# usb.net
KiCad netlist of a schematic drawn in Altium Designer
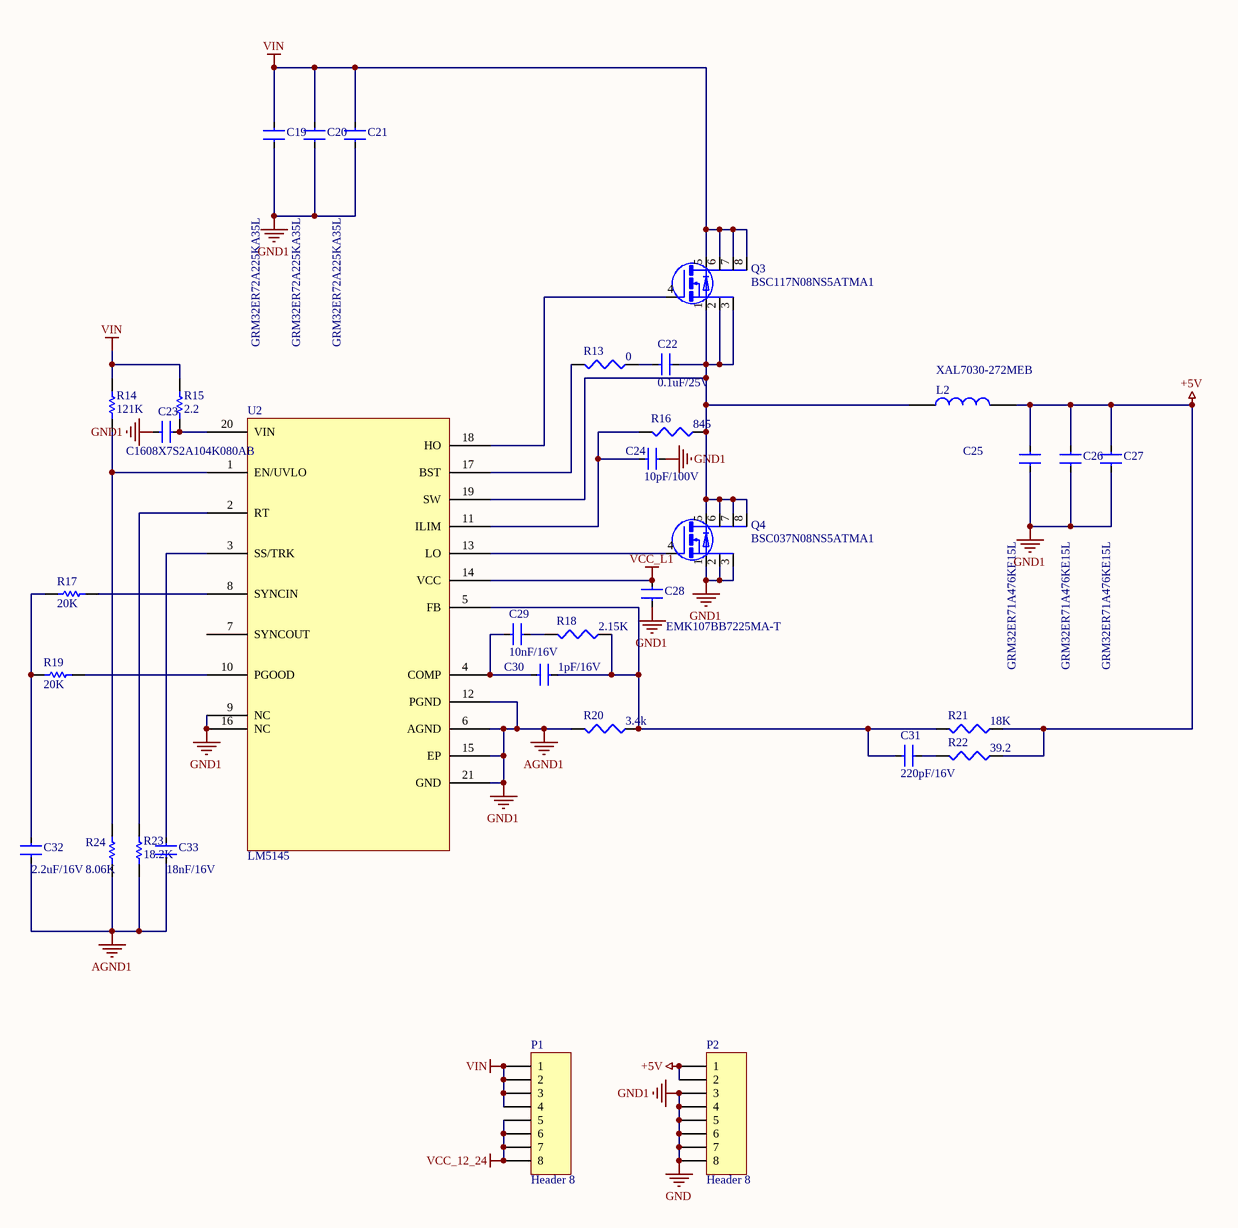
[diagram p0: usb.SchDoc]

(export (version "E")
  (design (tool "Eeschema 10.0.6"))
  (components
    (comp (ref "C19")
      (value "GRM32ER72A225KA35L")
      (footprint "1210C")
      (description "CCX85-103")
      (libsource (lib "无极性电容") (part "0.01UF"))
    )
    (comp (ref "C20")
      (value "GRM32ER72A225KA35L")
      (footprint "1210C")
      (description "CCX85-103")
      (libsource (lib "无极性电容") (part "0.01UF"))
    )
    (comp (ref "C21")
      (value "GRM32ER72A225KA35L")
      (footprint "1210C")
      (description "CCX85-103")
      (libsource (lib "无极性电容") (part "0.01UF"))
    )
    (comp (ref "C22")
      (value "0.1uF/25V")
      (footprint "0603C")
      (description "CCX85-103")
      (libsource (lib "无极性电容") (part "0.01UF"))
    )
    (comp (ref "C23")
      (value "C1608X7S2A104K080AB")
      (footprint "0603C")
      (description "CCX85-103")
      (libsource (lib "无极性电容") (part "0.01UF"))
    )
    (comp (ref "C24")
      (value "10pF/100V")
      (footprint "0603C")
      (description "CCX85-103")
      (libsource (lib "无极性电容") (part "0.01UF"))
    )
    (comp (ref "C25")
      (value "GRM32ER71A476KE15L")
      (footprint "1210C")
      (description "CCX85-103")
      (libsource (lib "无极性电容") (part "0.01UF"))
    )
    (comp (ref "C26")
      (value "GRM32ER71A476KE15L")
      (footprint "1210C")
      (description "CCX85-103")
      (libsource (lib "无极性电容") (part "0.01UF"))
    )
    (comp (ref "C27")
      (value "GRM32ER71A476KE15L")
      (footprint "1210C")
      (description "CCX85-103")
      (libsource (lib "无极性电容") (part "0.01UF"))
    )
    (comp (ref "C28")
      (value "EMK107BB7225MA-T")
      (footprint "0603C")
      (description "CCX85-103")
      (libsource (lib "无极性电容") (part "0.01UF"))
    )
    (comp (ref "C29")
      (value "10nF/16V")
      (footprint "0603C")
      (description "CCX85-103")
      (libsource (lib "无极性电容") (part "0.01UF"))
    )
    (comp (ref "C30")
      (value "1pF/16V")
      (footprint "0603C")
      (description "CCX85-103")
      (libsource (lib "无极性电容") (part "0.01UF"))
    )
    (comp (ref "C31")
      (value "220pF/16V")
      (footprint "0603C")
      (description "CCX85-103")
      (libsource (lib "无极性电容") (part "0.01UF"))
    )
    (comp (ref "C32")
      (value "2.2uF/16V")
      (footprint "0603C")
      (description "CCX85-103")
      (libsource (lib "无极性电容") (part "0.01UF"))
    )
    (comp (ref "C33")
      (value "18nF/16V")
      (footprint "0603C")
      (description "CCX85-103")
      (libsource (lib "无极性电容") (part "0.01UF"))
    )
    (comp (ref "L2") (value "XAL7030-272MEB") (footprint "XAL7030") (libsource (lib "*") (part "INDUCTOR")))
    (comp (ref "P1")
      (value "Header 8")
      (footprint "CH3.96-8P")
      (description "Header, 8-Pin")
      (fields (field (name "PUBLISHER") "Altium Limited"))
      (libsource (lib "Miscellaneous Connectors") (part "Header 8"))
    )
    (comp (ref "P2")
      (value "Header 8")
      (footprint "CH3.96-8P")
      (description "Header, 8-Pin")
      (fields (field (name "PUBLISHER") "Altium Limited"))
      (libsource (lib "Miscellaneous Connectors") (part "Header 8"))
    )
    (comp (ref "Q3")
      (value "BSC117N08NS5ATMA1")
      (footprint "PowerPAK SO-8")
      (description "Si4004DY")
      (libsource (lib "Schlib_20110825") (part "Si4004DY"))
    )
    (comp (ref "Q4")
      (value "BSC037N08NS5ATMA1")
      (footprint "PowerPAK SO-8")
      (description "Si4004DY")
      (libsource (lib "Schlib_20110825") (part "Si4004DY"))
    )
    (comp (ref "R13")
      (value "0")
      (footprint "0603R")
      (description "Resistor")
      (fields (field (name "PUBLISHER") "Altium Limited"))
      (libsource (lib "SM") (part "Res3"))
    )
    (comp (ref "R14")
      (value "121K")
      (footprint "0805R")
      (description "Semiconductor Resistor")
      (fields (field (name "PUBLISHER") "Altium Limited"))
      (libsource (lib "Miscellaneous Devices") (part "Res Semi"))
    )
    (comp (ref "R15")
      (value "2.2")
      (footprint "0603R")
      (description "Semiconductor Resistor")
      (fields (field (name "PUBLISHER") "Altium Limited"))
      (libsource (lib "Miscellaneous Devices") (part "Res Semi"))
    )
    (comp (ref "R16")
      (value "845")
      (footprint "0603R")
      (description "Resistor")
      (fields (field (name "PUBLISHER") "Altium Limited"))
      (libsource (lib "SM") (part "Res3"))
    )
    (comp (ref "R17")
      (value "20K")
      (footprint "0603R")
      (description "Semiconductor Resistor")
      (fields (field (name "PUBLISHER") "Altium Limited"))
      (libsource (lib "Miscellaneous Devices") (part "Res Semi"))
    )
    (comp (ref "R18")
      (value "2.15K")
      (footprint "0603R")
      (description "Resistor")
      (fields (field (name "PUBLISHER") "Altium Limited"))
      (libsource (lib "SM") (part "Res3"))
    )
    (comp (ref "R19")
      (value "20K")
      (footprint "0603R")
      (description "Semiconductor Resistor")
      (fields (field (name "PUBLISHER") "Altium Limited"))
      (libsource (lib "Miscellaneous Devices") (part "Res Semi"))
    )
    (comp (ref "R20")
      (value "3.4k")
      (footprint "0603R")
      (description "Resistor")
      (fields (field (name "PUBLISHER") "Altium Limited"))
      (libsource (lib "SM") (part "Res3"))
    )
    (comp (ref "R21")
      (value "18K")
      (footprint "0603R")
      (description "Resistor")
      (fields (field (name "PUBLISHER") "Altium Limited"))
      (libsource (lib "SM") (part "Res3"))
    )
    (comp (ref "R22")
      (value "39.2")
      (footprint "0603R")
      (description "Resistor")
      (fields (field (name "PUBLISHER") "Altium Limited"))
      (libsource (lib "SM") (part "Res3"))
    )
    (comp (ref "R23")
      (value "18.2K")
      (footprint "0603R")
      (description "Semiconductor Resistor")
      (fields (field (name "PUBLISHER") "Altium Limited"))
      (libsource (lib "Miscellaneous Devices") (part "Res Semi"))
    )
    (comp (ref "R24")
      (value "8.06K")
      (footprint "0603R")
      (description "Semiconductor Resistor")
      (fields (field (name "PUBLISHER") "Altium Limited"))
      (libsource (lib "Miscellaneous Devices") (part "Res Semi"))
    )
    (comp (ref "U2")
      (value "LM5145")
      (footprint "QFN050P600-8N")
      (libsource (lib "Schlib_20110825") (part "LM5145"))
    )
  )
  (nets
    (net (code "1") (name "+5V") (class "Default")
      (node (ref "C25") (pin "1") (pinfunction "1_1") (pintype "passive"))
      (node (ref "C26") (pin "1") (pinfunction "1_1") (pintype "passive"))
      (node (ref "C27") (pin "1") (pinfunction "1_1") (pintype "passive"))
      (node (ref "L2") (pin "2") (pinfunction "2_2") (pintype "passive"))
      (node (ref "P2") (pin "1") (pinfunction "1_1") (pintype "passive"))
      (node (ref "P2") (pin "2") (pinfunction "2_2") (pintype "passive"))
      (node (ref "R21") (pin "1") (pinfunction "1_1") (pintype "passive"))
      (node (ref "R22") (pin "1") (pinfunction "1_1") (pintype "passive"))
    )
    (net (code "2") (name "AGND1") (class "Default")
      (node (ref "C19") (pin "2") (pinfunction "2_2") (pintype "passive"))
      (node (ref "C20") (pin "2") (pinfunction "2_2") (pintype "passive"))
      (node (ref "C21") (pin "2") (pinfunction "2_2") (pintype "passive"))
      (node (ref "C23") (pin "1") (pinfunction "1_1") (pintype "passive"))
      (node (ref "C24") (pin "1") (pinfunction "1_1") (pintype "passive"))
      (node (ref "C25") (pin "2") (pinfunction "2_2") (pintype "passive"))
      (node (ref "C26") (pin "2") (pinfunction "2_2") (pintype "passive"))
      (node (ref "C27") (pin "2") (pinfunction "2_2") (pintype "passive"))
      (node (ref "C28") (pin "2") (pinfunction "2_2") (pintype "passive"))
      (node (ref "C32") (pin "2") (pinfunction "2_2") (pintype "passive"))
      (node (ref "C33") (pin "2") (pinfunction "2_2") (pintype "passive"))
      (node (ref "P2") (pin "3") (pinfunction "3_3") (pintype "passive"))
      (node (ref "P2") (pin "4") (pinfunction "4_4") (pintype "passive"))
      (node (ref "P2") (pin "5") (pinfunction "5_5") (pintype "passive"))
      (node (ref "P2") (pin "6") (pinfunction "6_6") (pintype "passive"))
      (node (ref "P2") (pin "7") (pinfunction "7_7") (pintype "passive"))
      (node (ref "P2") (pin "8") (pinfunction "8_8") (pintype "passive"))
      (node (ref "Q4") (pin "1") (pinfunction "S_1") (pintype "passive"))
      (node (ref "Q4") (pin "2") (pinfunction "S_2") (pintype "passive"))
      (node (ref "Q4") (pin "3") (pinfunction "S_3") (pintype "passive"))
      (node (ref "R20") (pin "2") (pinfunction "2_2") (pintype "passive"))
      (node (ref "R23") (pin "1") (pinfunction "1_1") (pintype "passive"))
      (node (ref "R24") (pin "1") (pinfunction "1_1") (pintype "passive"))
      (node (ref "U2") (pin "12") (pinfunction "PGND_12") (pintype "passive"))
      (node (ref "U2") (pin "15") (pinfunction "EP_15") (pintype "passive"))
      (node (ref "U2") (pin "16") (pinfunction "NC_16") (pintype "passive"))
      (node (ref "U2") (pin "21") (pinfunction "GND_21") (pintype "passive"))
      (node (ref "U2") (pin "6") (pinfunction "AGND_6") (pintype "passive"))
      (node (ref "U2") (pin "9") (pinfunction "NC_9") (pintype "passive"))
    )
    (net (code "3") (name "Net-(C22-Pad1)") (class "Default")
      (node (ref "C22") (pin "1") (pinfunction "1_1") (pintype "passive"))
      (node (ref "R13") (pin "1") (pinfunction "1_1") (pintype "passive"))
    )
    (net (code "4") (name "Net-(C29-Pad2)") (class "Default")
      (node (ref "C29") (pin "2") (pinfunction "2_2") (pintype "passive"))
      (node (ref "R18") (pin "2") (pinfunction "2_2") (pintype "passive"))
    )
    (net (code "5") (name "Net-(C31-Pad2)") (class "Default")
      (node (ref "C31") (pin "2") (pinfunction "2_2") (pintype "passive"))
      (node (ref "R22") (pin "2") (pinfunction "2_2") (pintype "passive"))
    )
    (net (code "6") (name "Net-(C32-Pad1)") (class "Default")
      (node (ref "C32") (pin "1") (pinfunction "1_1") (pintype "passive"))
      (node (ref "R17") (pin "2") (pinfunction "2_2") (pintype "passive"))
      (node (ref "R19") (pin "2") (pinfunction "2_2") (pintype "passive"))
    )
    (net (code "7") (name "Net-(Q3-G)") (class "Default")
      (node (ref "Q3") (pin "4") (pinfunction "G_4") (pintype "passive"))
      (node (ref "U2") (pin "18") (pinfunction "HO_18") (pintype "passive"))
    )
    (net (code "8") (name "Net-(Q4-G)") (class "Default")
      (node (ref "Q4") (pin "4") (pinfunction "G_4") (pintype "passive"))
      (node (ref "U2") (pin "13") (pinfunction "LO_13") (pintype "passive"))
    )
    (net (code "9") (name "Net-(U2-BST)") (class "Default")
      (node (ref "R13") (pin "2") (pinfunction "2_2") (pintype "passive"))
      (node (ref "U2") (pin "17") (pinfunction "BST_17") (pintype "passive"))
    )
    (net (code "10") (name "Net-(U2-COMP)") (class "Default")
      (node (ref "C29") (pin "1") (pinfunction "1_1") (pintype "passive"))
      (node (ref "C30") (pin "1") (pinfunction "1_1") (pintype "passive"))
      (node (ref "U2") (pin "4") (pinfunction "COMP_4") (pintype "passive"))
    )
    (net (code "11") (name "Net-(U2-EN{slash}UVLO)") (class "Default")
      (node (ref "R14") (pin "1") (pinfunction "1_1") (pintype "passive"))
      (node (ref "R24") (pin "2") (pinfunction "2_2") (pintype "passive"))
      (node (ref "U2") (pin "1") (pinfunction "EN/UVLO_1") (pintype "passive"))
    )
    (net (code "12") (name "Net-(U2-FB)") (class "Default")
      (node (ref "C30") (pin "2") (pinfunction "2_2") (pintype "passive"))
      (node (ref "C31") (pin "1") (pinfunction "1_1") (pintype "passive"))
      (node (ref "R18") (pin "1") (pinfunction "1_1") (pintype "passive"))
      (node (ref "R20") (pin "1") (pinfunction "1_1") (pintype "passive"))
      (node (ref "R21") (pin "2") (pinfunction "2_2") (pintype "passive"))
      (node (ref "U2") (pin "5") (pinfunction "FB_5") (pintype "passive"))
    )
    (net (code "13") (name "Net-(U2-ILIM)") (class "Default")
      (node (ref "C24") (pin "2") (pinfunction "2_2") (pintype "passive"))
      (node (ref "R16") (pin "2") (pinfunction "2_2") (pintype "passive"))
      (node (ref "U2") (pin "11") (pinfunction "ILIM_11") (pintype "passive"))
    )
    (net (code "14") (name "Net-(U2-PGOOD)") (class "Default")
      (node (ref "R19") (pin "1") (pinfunction "1_1") (pintype "passive"))
      (node (ref "U2") (pin "10") (pinfunction "PGOOD_10") (pintype "passive"))
    )
    (net (code "15") (name "Net-(U2-RT)") (class "Default")
      (node (ref "R23") (pin "2") (pinfunction "2_2") (pintype "passive"))
      (node (ref "U2") (pin "2") (pinfunction "RT_2") (pintype "passive"))
    )
    (net (code "16") (name "Net-(U2-SS{slash}TRK)") (class "Default")
      (node (ref "C33") (pin "1") (pinfunction "1_1") (pintype "passive"))
      (node (ref "U2") (pin "3") (pinfunction "SS/TRK_3") (pintype "passive"))
    )
    (net (code "17") (name "Net-(U2-SW)") (class "Default")
      (node (ref "C22") (pin "2") (pinfunction "2_2") (pintype "passive"))
      (node (ref "L2") (pin "1") (pinfunction "1_1") (pintype "passive"))
      (node (ref "Q3") (pin "1") (pinfunction "S_1") (pintype "passive"))
      (node (ref "Q3") (pin "2") (pinfunction "S_2") (pintype "passive"))
      (node (ref "Q3") (pin "3") (pinfunction "S_3") (pintype "passive"))
      (node (ref "Q4") (pin "5") (pinfunction "D_5") (pintype "passive"))
      (node (ref "Q4") (pin "6") (pinfunction "D_6") (pintype "passive"))
      (node (ref "Q4") (pin "7") (pinfunction "D_7") (pintype "passive"))
      (node (ref "Q4") (pin "8") (pinfunction "D_8") (pintype "passive"))
      (node (ref "R16") (pin "1") (pinfunction "1_1") (pintype "passive"))
      (node (ref "U2") (pin "19") (pinfunction "SW_19") (pintype "passive"))
    )
    (net (code "18") (name "Net-(U2-SYNCIN)") (class "Default")
      (node (ref "R17") (pin "1") (pinfunction "1_1") (pintype "passive"))
      (node (ref "U2") (pin "8") (pinfunction "SYNCIN_8") (pintype "passive"))
    )
    (net (code "19") (name "Net-(U2-VIN)") (class "Default")
      (node (ref "C23") (pin "2") (pinfunction "2_2") (pintype "passive"))
      (node (ref "R15") (pin "2") (pinfunction "2_2") (pintype "passive"))
      (node (ref "U2") (pin "20") (pinfunction "VIN_20") (pintype "passive"))
    )
    (net (code "20") (name "VCC_12_24") (class "Default")
      (node (ref "P1") (pin "5") (pinfunction "5_5") (pintype "passive"))
      (node (ref "P1") (pin "6") (pinfunction "6_6") (pintype "passive"))
      (node (ref "P1") (pin "7") (pinfunction "7_7") (pintype "passive"))
      (node (ref "P1") (pin "8") (pinfunction "8_8") (pintype "passive"))
    )
    (net (code "21") (name "VCC_L1") (class "Default")
      (node (ref "C28") (pin "1") (pinfunction "1_1") (pintype "passive"))
      (node (ref "U2") (pin "14") (pinfunction "VCC_14") (pintype "passive"))
    )
    (net (code "22") (name "VIN") (class "Default")
      (node (ref "C19") (pin "1") (pinfunction "1_1") (pintype "passive"))
      (node (ref "C20") (pin "1") (pinfunction "1_1") (pintype "passive"))
      (node (ref "C21") (pin "1") (pinfunction "1_1") (pintype "passive"))
      (node (ref "P1") (pin "1") (pinfunction "1_1") (pintype "passive"))
      (node (ref "P1") (pin "2") (pinfunction "2_2") (pintype "passive"))
      (node (ref "P1") (pin "3") (pinfunction "3_3") (pintype "passive"))
      (node (ref "P1") (pin "4") (pinfunction "4_4") (pintype "passive"))
      (node (ref "Q3") (pin "5") (pinfunction "D_5") (pintype "passive"))
      (node (ref "Q3") (pin "6") (pinfunction "D_6") (pintype "passive"))
      (node (ref "Q3") (pin "7") (pinfunction "D_7") (pintype "passive"))
      (node (ref "Q3") (pin "8") (pinfunction "D_8") (pintype "passive"))
      (node (ref "R14") (pin "2") (pinfunction "2_2") (pintype "passive"))
      (node (ref "R15") (pin "1") (pinfunction "1_1") (pintype "passive"))
    )
    (net (code "23") (name "unconnected-(U2-SYNCOUT-Pad7)") (class "Default")
      (node (ref "U2") (pin "7") (pinfunction "SYNCOUT_7") (pintype "passive"))
    )
  )
)
